# Power_Internal.net
KiCad netlist of a schematic drawn in Altium Designer
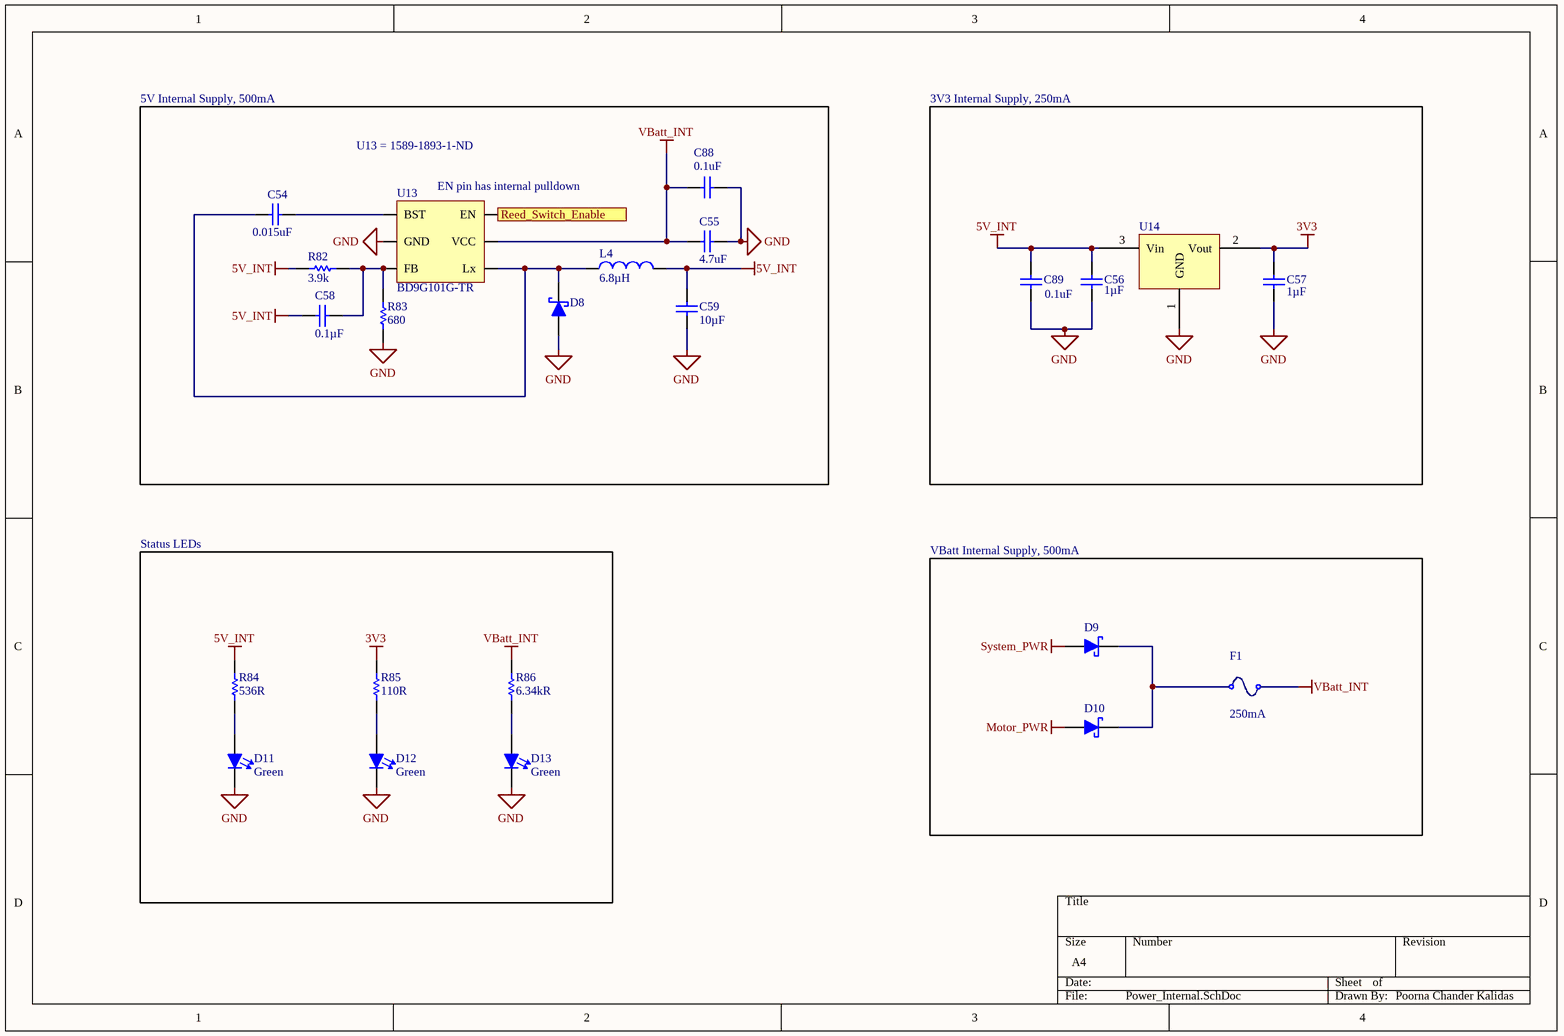
[diagram p0: Power_Internal.SchDoc]

(export (version "E")
  (design (tool "Eeschema 10.0.6"))
  (components
    (comp (ref "C54")
      (value "0.015uF")
      (footprint "CAPC1608N(0603\")")
      (description "Capacitor, Ceramic, 50V, +/-10%, 0603 SMD, X7R")
      (fields
        (field (name "Comment") "0.015uF 50V 0603 SMD, Ceramic")
        (field (name "CREATED BY") "Lyden Smith")
      )
      (libsource (lib "") (part "Symbol_6"))
    )
    (comp (ref "C55")
      (value "4.7uF")
      (footprint "CAPC3216N(1206\")")
      (description "Capacitor, Ceramic, 50V, +/- 10%, 1206 SMD, X7R")
      (fields
        (field (name "Comment") "4.7uF 50V 1206 SMD, Ceramic")
        (field (name "CREATED BY") "Lyden Smith")
      )
      (libsource (lib "") (part "Symbol_6"))
    )
    (comp (ref "C56")
      (value "1µF")
      (footprint "CAPC1608N(0603\")")
      (description "Capacitor, Ceramic, 25V, +/- 10%, 0603 SMD, X5R")
      (fields
        (field (name "MFG") "Murata-Electronics-North-America")
        (field (name "Comment") "1uF 25V 0603 SMD, Ceramic")
        (field (name "CREATED BY") "Andy Bates")
        (field (name "PUBLISHER") "AUVic")
      )
      (libsource (lib "") (part "Symbol_3"))
    )
    (comp (ref "C57")
      (value "1µF")
      (footprint "CAPC1608N(0603\")")
      (description "Capacitor, Ceramic, 25V, +/- 10%, 0603 SMD, X5R")
      (fields
        (field (name "MFG") "Murata-Electronics-North-America")
        (field (name "Comment") "1uF 25V 0603 SMD, Ceramic")
        (field (name "CREATED BY") "Andy Bates")
        (field (name "PUBLISHER") "AUVic")
      )
      (libsource (lib "") (part "Symbol_3"))
    )
    (comp (ref "C58")
      (value "0.1uF, 50V, 10%, X7R, 1608")
      (footprint "CAPC1608N(0603\")")
      (description "CAP CER 0.1UF 50V 10% X7R 1608 (0603)")
      (fields
        (field (name "MANUFACTURER") "Samsung Electro-Mechanics America, Inc")
        (field (name "MANUFACTURER PART NUMBER") "CL10B104KB8SFNC")
        (field (name "CAPACITANCE") "0.1µF")
      )
      (libsource (lib "") (part "Symbol_3"))
    )
    (comp (ref "C59")
      (value "10µF")
      (footprint "CAPC2012N(0805\")")
      (description "Capacitor, Ceramic, 10V, +/- 10%, 0805 SMD, X5R")
      (fields
        (field (name "Comment") "10uF 10V 0805 SMD, Ceramic")
        (field (name "PUBLISHER") "AUVic")
        (field (name "MADE BY") "Andy Bates")
      )
      (libsource (lib "") (part "Symbol_4"))
    )
    (comp (ref "C88")
      (value "CL10B104JB8NNNC")
      (footprint "FP-CL10-0_1-IPC_A")
      (description "CAP CER 0.1UF 50V X7R 0603")
      (fields
        (field (name "CAPACITANCE") "0.1uF")
        (field (name "VOLTAGE") "50V")
        (field (name "TOLERANCE") "5%")
      )
      (libsource (lib "AUVIC") (part "CAP-NP-2"))
    )
    (comp (ref "C89")
      (value "CL10B104JB8NNNC")
      (footprint "FP-CL10-0_1-IPC_A")
      (description "CAP CER 0.1UF 50V X7R 0603")
      (fields
        (field (name "CAPACITANCE") "0.1uF")
        (field (name "VOLTAGE") "50V")
        (field (name "TOLERANCE") "5%")
      )
      (libsource (lib "AUVIC") (part "CAP-NP-2"))
    )
    (comp (ref "D8")
      (value "RB060M-60TR")
      (footprint "SOD-123")
      (description "Diode, Schottky, 60V, 2A")
      (fields (field (name "CREATED BY") "Lyden Smith"))
      (libsource (lib "AUVIC") (part "Symbol"))
    )
    (comp (ref "D9")
      (value "DSS14UTR")
      (footprint "SOD-123F")
      (description "Diode, Schottky, 40V, 1A")
      (fields (field (name "CREATED BY") "Robert Keen") (field (name "PUBLISHER") "AUVic"))
      (libsource (lib "AUVIC") (part "Symbol"))
    )
    (comp (ref "D10")
      (value "DSS14UTR")
      (footprint "SOD-123F")
      (description "Diode, Schottky, 40V, 1A")
      (fields (field (name "CREATED BY") "Robert Keen") (field (name "PUBLISHER") "AUVic"))
      (libsource (lib "AUVIC") (part "Symbol"))
    )
    (comp (ref "D11")
      (value "LT Q39G-Q1OO-25-1")
      (footprint "FP-LB_Q39E-MFG")
      (description "LED GREEN DIFFUSED 0603 SMD")
      (fields (field (name "COLOR") "Green"))
      (libsource (lib "") (part "Symbol_2"))
    )
    (comp (ref "D12")
      (value "LT Q39G-Q1OO-25-1")
      (footprint "FP-LB_Q39E-MFG")
      (description "LED GREEN DIFFUSED 0603 SMD")
      (fields (field (name "COLOR") "Green"))
      (libsource (lib "") (part "Symbol_2"))
    )
    (comp (ref "D13")
      (value "LT Q39G-Q1OO-25-1")
      (footprint "FP-LB_Q39E-MFG")
      (description "LED GREEN DIFFUSED 0603 SMD")
      (fields (field (name "COLOR") "Green"))
      (libsource (lib "") (part "Symbol_2"))
    )
    (comp (ref "F1")
      (value "SMD Fuse, 250mA, 63V, 1206")
      (footprint "1206 SMD")
      (fields (field (name "CURRENT") "250mA") (field (name "CREATED BY") "Lyden Smith"))
      (libsource (lib "") (part "Symbol_5"))
    )
    (comp (ref "L4")
      (value "6.8µH")
      (footprint "NR4018T6R8M Inductor")
      (description "6.8uH 1.06A")
      (fields (field (name "Comment") "NR4018T6R8M") (field (name "CREATED BY") "Lyden Smith"))
      (libsource (lib "") (part "Symbol_7"))
    )
    (comp (ref "R82")
      (value "3.9k")
      (footprint "RESC2012N(0805\")")
      (description "3.9k, 5%, 1/8W, 0805 SMD")
      (fields (field (name "CREATED BY") "Lyden Smith"))
      (libsource (lib "") (part "Symbol_1"))
    )
    (comp (ref "R83")
      (value "680")
      (footprint "RESC2012N(0805\")")
      (description "680, 5%, 1/8W, 0805 SMD")
      (fields (field (name "CREATED BY") "Lyden Smith"))
      (libsource (lib "") (part "Symbol_1"))
    )
    (comp (ref "R84")
      (value "ERJ-3EKF5360V")
      (footprint "RESC1608X55X30ML15T15")
      (description "SMD Chip Resistor, 0603 [1608 Metric], 536 ohm, ERJ3EK Series, 75 V, Thick Film, 100 mW")
      (fields (field (name "TOLERANCE") "1%") (field (name "RESISTANCE") "536R"))
      (libsource (lib "AUVIC") (part "RES"))
    )
    (comp (ref "R85")
      (value "RC0603FR-07110RL")
      (footprint "RESC1608X55X25ML10T15")
      (description "RES SMD 110 OHM 1% 1/10W 0603")
      (fields (field (name "TOLERANCE") "1%") (field (name "RESISTANCE") "110R"))
      (libsource (lib "AUVIC") (part "RES"))
    )
    (comp (ref "R86")
      (value "CRCW06036K34FKEA")
      (footprint "RESC1609X50X30ML10T20")
      (fields (field (name "RESISTANCE") "6.34kR") (field (name "TOLERANCE") "1%"))
      (libsource (lib "AUVIC") (part "RES"))
    )
    (comp (ref "U13")
      (value "BD9G101G-TR")
      (footprint "SOT23-6_N")
      (description "DC-DC Regulator, 6V-42V in, 1V-29.4V out, 500mA")
      (fields (field (name "CREATED BY") "Lyden Smith"))
      (libsource (lib "AUVIC") (part "BD9G101G-TR"))
    )
    (comp (ref "U14")
      (value "3.3V 250mA Linear Reg LDO")
      (footprint "SOT95P245X110-3N")
      (description "IC REG LINEAR 3.3V 250MA SOT23-3")
      (fields (field (name "CREATED BY") "Poorna Chander Kalidas"))
      (libsource (lib "AUVIC") (part "3.3V 250mA Linear Reg LDO"))
    )
  )
  (nets
    (net (code "1") (name "/Reed_Switch_Enable") (class "Default")
      (node (ref "U13") (pin "4") (pinfunction "EN_4") (pintype "passive"))
    )
    (net (code "2") (name "3V3") (class "Default")
      (node (ref "C57") (pin "2") (pinfunction "Cathode_2") (pintype "passive"))
      (node (ref "R85") (pin "2") (pinfunction "2_2") (pintype "passive"))
      (node (ref "U14") (pin "2") (pinfunction "Vout_2") (pintype "power_in"))
    )
    (net (code "3") (name "5V_INT") (class "Default")
      (node (ref "C56") (pin "2") (pinfunction "Cathode_2") (pintype "passive"))
      (node (ref "C58") (pin "1") (pinfunction "Anode_1") (pintype "passive"))
      (node (ref "C59") (pin "2") (pinfunction "Cathode_2") (pintype "passive"))
      (node (ref "C89") (pin "1") (pinfunction "1_1") (pintype "passive"))
      (node (ref "L4") (pin "2") (pinfunction "2_2") (pintype "passive"))
      (node (ref "R82") (pin "1") (pinfunction "1_1") (pintype "passive"))
      (node (ref "R84") (pin "1") (pinfunction "1_1") (pintype "passive"))
      (node (ref "U14") (pin "3") (pinfunction "Vin_3") (pintype "power_in"))
    )
    (net (code "4") (name "GND") (class "Default")
      (node (ref "C55") (pin "1") (pinfunction "1_1") (pintype "passive"))
      (node (ref "C56") (pin "1") (pinfunction "Anode_1") (pintype "passive"))
      (node (ref "C57") (pin "1") (pinfunction "Anode_1") (pintype "passive"))
      (node (ref "C59") (pin "1") (pinfunction "Anode_1") (pintype "passive"))
      (node (ref "C88") (pin "2") (pinfunction "2_2") (pintype "passive"))
      (node (ref "C89") (pin "2") (pinfunction "2_2") (pintype "passive"))
      (node (ref "D11") (pin "1") (pinfunction "Cathode_1") (pintype "passive"))
      (node (ref "D12") (pin "1") (pinfunction "Cathode_1") (pintype "passive"))
      (node (ref "D13") (pin "1") (pinfunction "Cathode_1") (pintype "passive"))
      (node (ref "D8") (pin "A") (pinfunction "Anode_A") (pintype "passive"))
      (node (ref "R83") (pin "1") (pinfunction "1_1") (pintype "passive"))
      (node (ref "U13") (pin "2") (pinfunction "GND_2") (pintype "power_in"))
      (node (ref "U14") (pin "1") (pinfunction "GND_1") (pintype "power_in"))
    )
    (net (code "5") (name "Motor_PWR") (class "Default")
      (node (ref "D10") (pin "A") (pinfunction "Anode_A") (pintype "passive"))
    )
    (net (code "6") (name "Net-(C58-Cathode)") (class "Default")
      (node (ref "C58") (pin "2") (pinfunction "Cathode_2") (pintype "passive"))
      (node (ref "R82") (pin "2") (pinfunction "2_2") (pintype "passive"))
      (node (ref "R83") (pin "2") (pinfunction "2_2") (pintype "passive"))
      (node (ref "U13") (pin "3") (pinfunction "FB_3") (pintype "power_in"))
    )
    (net (code "7") (name "Net-(D8-Cathode)") (class "Default")
      (node (ref "C54") (pin "1") (pinfunction "1_1") (pintype "passive"))
      (node (ref "D8") (pin "K") (pinfunction "Cathode_K") (pintype "passive"))
      (node (ref "L4") (pin "1") (pinfunction "1_1") (pintype "passive"))
      (node (ref "U13") (pin "6") (pinfunction "Lx_6") (pintype "power_in"))
    )
    (net (code "8") (name "Net-(D10-Cathode)") (class "Default")
      (node (ref "D10") (pin "K") (pinfunction "Cathode_K") (pintype "passive"))
      (node (ref "D9") (pin "K") (pinfunction "Cathode_K") (pintype "passive"))
      (node (ref "F1") (pin "2") (pinfunction "2_2") (pintype "passive"))
    )
    (net (code "9") (name "Net-(D11-Anode)") (class "Default")
      (node (ref "D11") (pin "2") (pinfunction "Anode_2") (pintype "passive"))
      (node (ref "R84") (pin "2") (pinfunction "2_2") (pintype "passive"))
    )
    (net (code "10") (name "Net-(D12-Anode)") (class "Default")
      (node (ref "D12") (pin "2") (pinfunction "Anode_2") (pintype "passive"))
      (node (ref "R85") (pin "1") (pinfunction "1_1") (pintype "passive"))
    )
    (net (code "11") (name "Net-(D13-Anode)") (class "Default")
      (node (ref "D13") (pin "2") (pinfunction "Anode_2") (pintype "passive"))
      (node (ref "R86") (pin "1") (pinfunction "1_1") (pintype "passive"))
    )
    (net (code "12") (name "Net-(U13-BST)") (class "Default")
      (node (ref "C54") (pin "2") (pinfunction "2_2") (pintype "passive"))
      (node (ref "U13") (pin "1") (pinfunction "BST_1") (pintype "power_in"))
    )
    (net (code "13") (name "System_PWR") (class "Default")
      (node (ref "D9") (pin "A") (pinfunction "Anode_A") (pintype "passive"))
    )
    (net (code "14") (name "VBatt_INT") (class "Default")
      (node (ref "C55") (pin "2") (pinfunction "2_2") (pintype "passive"))
      (node (ref "C88") (pin "1") (pinfunction "1_1") (pintype "passive"))
      (node (ref "F1") (pin "1") (pinfunction "1_1") (pintype "passive"))
      (node (ref "R86") (pin "2") (pinfunction "2_2") (pintype "passive"))
      (node (ref "U13") (pin "5") (pinfunction "VCC_5") (pintype "power_in"))
    )
  )
)
